# L293.net
KiCad netlist of a schematic drawn in EAGLE
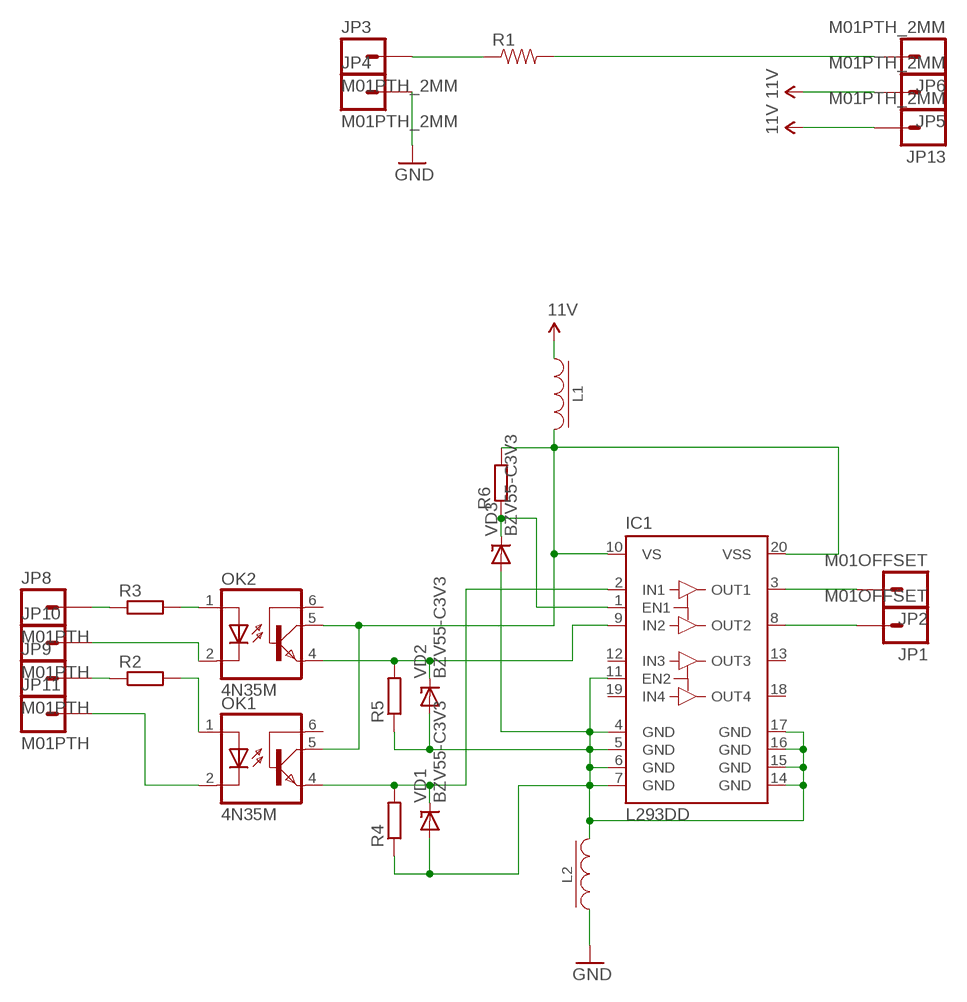
[diagram p0: schematic, sheet 1]

(export (version "E")
  (design (tool "Eeschema 10.0.6"))
  (components
    (comp (ref "IC1")
      (value "L293DD")
      (footprint "eagle-import:SO20")
      (libsource (lib "eagle-import") (part "L293DD"))
    )
    (comp (ref "JP1")
      (value "M01OFFSET")
      (footprint "eagle-import:1X01_OFFSET")
      (libsource (lib "eagle-import") (part "M01OFFSET"))
    )
    (comp (ref "JP2")
      (value "M01OFFSET")
      (footprint "eagle-import:1X01_OFFSET")
      (libsource (lib "eagle-import") (part "M01OFFSET"))
    )
    (comp (ref "JP3")
      (value "M01PTH_2MM")
      (footprint "eagle-import:1X01_2MM")
      (libsource (lib "eagle-import") (part "M01PTH_2MM"))
    )
    (comp (ref "JP4")
      (value "M01PTH_2MM")
      (footprint "eagle-import:1X01_2MM")
      (libsource (lib "eagle-import") (part "M01PTH_2MM"))
    )
    (comp (ref "JP5")
      (value "M01PTH_2MM")
      (footprint "eagle-import:1X01_2MM")
      (libsource (lib "eagle-import") (part "M01PTH_2MM"))
    )
    (comp (ref "JP6")
      (value "M01PTH_2MM")
      (footprint "eagle-import:1X01_2MM")
      (libsource (lib "eagle-import") (part "M01PTH_2MM"))
    )
    (comp (ref "JP8")
      (value "M01PTH")
      (footprint "eagle-import:1X01")
      (libsource (lib "eagle-import") (part "M01PTH"))
    )
    (comp (ref "JP9")
      (value "M01PTH")
      (footprint "eagle-import:1X01")
      (libsource (lib "eagle-import") (part "M01PTH"))
    )
    (comp (ref "JP10")
      (value "M01PTH")
      (footprint "eagle-import:1X01")
      (libsource (lib "eagle-import") (part "M01PTH"))
    )
    (comp (ref "JP11")
      (value "M01PTH")
      (footprint "eagle-import:1X01")
      (libsource (lib "eagle-import") (part "M01PTH"))
    )
    (comp (ref "JP13")
      (value "M01PTH_2MM")
      (footprint "eagle-import:1X01_2MM")
      (libsource (lib "eagle-import") (part "M01PTH_2MM"))
    )
    (comp (ref "L1")
      (value "DRA127")
      (footprint "eagle-import:DRA127")
      (libsource (lib "eagle-import") (part "DRA127"))
    )
    (comp (ref "L2")
      (value "DRA127")
      (footprint "eagle-import:DRA127")
      (libsource (lib "eagle-import") (part "DRA127"))
    )
    (comp (ref "OK1")
      (value "4N35M")
      (footprint "eagle-import:DIL06")
      (fields (field (name "MPN") "4N35-M"))
      (libsource (lib "eagle-import") (part "4N?M35"))
    )
    (comp (ref "OK2")
      (value "4N35M")
      (footprint "eagle-import:DIL06")
      (fields (field (name "MPN") "4N35-M"))
      (libsource (lib "eagle-import") (part "4N?M35"))
    )
    (comp (ref "R1")
      (value "RESISTOR2512")
      (footprint "eagle-import:R2512")
      (libsource (lib "eagle-import") (part "RESISTOR2512"))
    )
    (comp (ref "R2")
      (value "RESISTOR0805")
      (footprint "eagle-import:0805")
      (libsource (lib "eagle-import") (part "RESISTOR0805"))
    )
    (comp (ref "R3")
      (value "RESISTOR0805")
      (footprint "eagle-import:0805")
      (libsource (lib "eagle-import") (part "RESISTOR0805"))
    )
    (comp (ref "R4")
      (value "RESISTOR0805")
      (footprint "eagle-import:0805")
      (libsource (lib "eagle-import") (part "RESISTOR0805"))
    )
    (comp (ref "R5")
      (value "RESISTOR0805")
      (footprint "eagle-import:0805")
      (libsource (lib "eagle-import") (part "RESISTOR0805"))
    )
    (comp (ref "R6")
      (value "RESISTOR0805")
      (footprint "eagle-import:0805")
      (libsource (lib "eagle-import") (part "RESISTOR0805"))
    )
    (comp (ref "VD1")
      (value "BZV55-C3V3")
      (footprint "eagle-import:SOD80C")
      (fields (field (name "PARTNO") "?"))
      (libsource (lib "eagle-import") (part "BZV55-C3V3"))
    )
    (comp (ref "VD2")
      (value "BZV55-C3V3")
      (footprint "eagle-import:SOD80C")
      (fields (field (name "PARTNO") "?"))
      (libsource (lib "eagle-import") (part "BZV55-C3V3"))
    )
    (comp (ref "VD3")
      (value "BZV55-C3V3")
      (footprint "eagle-import:SOD80C")
      (fields (field (name "PARTNO") "?"))
      (libsource (lib "eagle-import") (part "BZV55-C3V3"))
    )
  )
  (nets
    (net (code "1") (name "11V") (class "Default")
      (node (ref "JP13") (pin "1") (pinfunction "1_1") (pintype "passive"))
      (node (ref "JP5") (pin "1") (pinfunction "1_1") (pintype "passive"))
      (node (ref "L1") (pin "1") (pinfunction "1_1") (pintype "passive"))
    )
    (net (code "2") (name "GND") (class "Default")
      (node (ref "JP4") (pin "1") (pinfunction "1_1") (pintype "passive"))
      (node (ref "L2") (pin "1") (pinfunction "1_1") (pintype "passive"))
    )
    (net (code "3") (name "Net-(IC1-EN1)") (class "Default")
      (node (ref "IC1") (pin "1") (pinfunction "EN1_1") (pintype "input"))
      (node (ref "R6") (pin "1") (pinfunction "1_1") (pintype "passive"))
      (node (ref "VD3") (pin "C") (pinfunction "C_C") (pintype "passive"))
    )
    (net (code "4") (name "Net-(IC1-EN2)") (class "Default")
      (node (ref "IC1") (pin "11") (pinfunction "EN2_11") (pintype "input"))
      (node (ref "IC1") (pin "14") (pinfunction "GND_14") (pintype "power_in"))
      (node (ref "IC1") (pin "15") (pinfunction "GND_15") (pintype "power_in"))
      (node (ref "IC1") (pin "16") (pinfunction "GND_16") (pintype "power_in"))
      (node (ref "IC1") (pin "17") (pinfunction "GND_17") (pintype "power_in"))
      (node (ref "IC1") (pin "4") (pinfunction "GND_4") (pintype "power_in"))
      (node (ref "IC1") (pin "5") (pinfunction "GND_5") (pintype "power_in"))
      (node (ref "IC1") (pin "6") (pinfunction "GND_6") (pintype "power_in"))
      (node (ref "IC1") (pin "7") (pinfunction "GND_7") (pintype "power_in"))
      (node (ref "L2") (pin "2") (pinfunction "2_2") (pintype "passive"))
      (node (ref "R4") (pin "1") (pinfunction "1_1") (pintype "passive"))
      (node (ref "R5") (pin "1") (pinfunction "1_1") (pintype "passive"))
      (node (ref "VD1") (pin "A") (pinfunction "A_A") (pintype "passive"))
      (node (ref "VD2") (pin "A") (pinfunction "A_A") (pintype "passive"))
      (node (ref "VD3") (pin "A") (pinfunction "A_A") (pintype "passive"))
    )
    (net (code "5") (name "Net-(IC1-IN1)") (class "Default")
      (node (ref "IC1") (pin "2") (pinfunction "IN1_2") (pintype "input"))
      (node (ref "OK1") (pin "4") (pinfunction "EMI_4") (pintype "passive"))
      (node (ref "R4") (pin "2") (pinfunction "2_2") (pintype "passive"))
      (node (ref "VD1") (pin "C") (pinfunction "C_C") (pintype "passive"))
    )
    (net (code "6") (name "Net-(IC1-IN2)") (class "Default")
      (node (ref "IC1") (pin "9") (pinfunction "IN2_9") (pintype "input"))
      (node (ref "OK2") (pin "4") (pinfunction "EMI_4") (pintype "passive"))
      (node (ref "R5") (pin "2") (pinfunction "2_2") (pintype "passive"))
      (node (ref "VD2") (pin "C") (pinfunction "C_C") (pintype "passive"))
    )
    (net (code "7") (name "Net-(IC1-OUT1)") (class "Default")
      (node (ref "IC1") (pin "3") (pinfunction "OUT1_3") (pintype "output"))
      (node (ref "JP2") (pin "1") (pinfunction "1_1") (pintype "passive"))
    )
    (net (code "8") (name "Net-(IC1-OUT2)") (class "Default")
      (node (ref "IC1") (pin "8") (pinfunction "OUT2_8") (pintype "output"))
      (node (ref "JP1") (pin "1") (pinfunction "1_1") (pintype "passive"))
    )
    (net (code "9") (name "Net-(IC1-VS)") (class "Default")
      (node (ref "IC1") (pin "10") (pinfunction "VS_10") (pintype "power_in"))
      (node (ref "IC1") (pin "20") (pinfunction "VSS_20") (pintype "power_in"))
      (node (ref "L1") (pin "2") (pinfunction "2_2") (pintype "passive"))
      (node (ref "OK1") (pin "5") (pinfunction "COL_5") (pintype "passive"))
      (node (ref "OK2") (pin "5") (pinfunction "COL_5") (pintype "passive"))
      (node (ref "R6") (pin "2") (pinfunction "2_2") (pintype "passive"))
    )
    (net (code "10") (name "Net-(JP3-Pad1)") (class "Default")
      (node (ref "JP3") (pin "1") (pinfunction "1_1") (pintype "passive"))
      (node (ref "R1") (pin "1") (pinfunction "1_1") (pintype "passive"))
    )
    (net (code "11") (name "Net-(JP6-Pad1)") (class "Default")
      (node (ref "JP6") (pin "1") (pinfunction "1_1") (pintype "passive"))
      (node (ref "R1") (pin "2") (pinfunction "2_2") (pintype "passive"))
    )
    (net (code "12") (name "Net-(JP8-Pad1)") (class "Default")
      (node (ref "JP8") (pin "1") (pinfunction "1_1") (pintype "passive"))
      (node (ref "R3") (pin "1") (pinfunction "1_1") (pintype "passive"))
    )
    (net (code "13") (name "Net-(JP9-Pad1)") (class "Default")
      (node (ref "JP9") (pin "1") (pinfunction "1_1") (pintype "passive"))
      (node (ref "R2") (pin "1") (pinfunction "1_1") (pintype "passive"))
    )
    (net (code "14") (name "Net-(OK1-A)") (class "Default")
      (node (ref "OK1") (pin "1") (pinfunction "A_1") (pintype "passive"))
      (node (ref "R2") (pin "2") (pinfunction "2_2") (pintype "passive"))
    )
    (net (code "15") (name "Net-(OK1-C)") (class "Default")
      (node (ref "JP11") (pin "1") (pinfunction "1_1") (pintype "passive"))
      (node (ref "OK1") (pin "2") (pinfunction "C_2") (pintype "passive"))
    )
    (net (code "16") (name "Net-(OK2-A)") (class "Default")
      (node (ref "OK2") (pin "1") (pinfunction "A_1") (pintype "passive"))
      (node (ref "R3") (pin "2") (pinfunction "2_2") (pintype "passive"))
    )
    (net (code "17") (name "Net-(OK2-C)") (class "Default")
      (node (ref "JP10") (pin "1") (pinfunction "1_1") (pintype "passive"))
      (node (ref "OK2") (pin "2") (pinfunction "C_2") (pintype "passive"))
    )
    (net (code "18") (name "unconnected-(IC1-IN3-Pad12)") (class "Default")
      (node (ref "IC1") (pin "12") (pinfunction "IN3_12") (pintype "input"))
    )
    (net (code "19") (name "unconnected-(IC1-IN4-Pad19)") (class "Default")
      (node (ref "IC1") (pin "19") (pinfunction "IN4_19") (pintype "input"))
    )
    (net (code "20") (name "unconnected-(IC1-OUT3-Pad13)") (class "Default")
      (node (ref "IC1") (pin "13") (pinfunction "OUT3_13") (pintype "output"))
    )
    (net (code "21") (name "unconnected-(IC1-OUT4-Pad18)") (class "Default")
      (node (ref "IC1") (pin "18") (pinfunction "OUT4_18") (pintype "output"))
    )
    (net (code "22") (name "unconnected-(OK1-BAS-Pad6)") (class "Default")
      (node (ref "OK1") (pin "6") (pinfunction "BAS_6") (pintype "passive"))
    )
    (net (code "23") (name "unconnected-(OK2-BAS-Pad6)") (class "Default")
      (node (ref "OK2") (pin "6") (pinfunction "BAS_6") (pintype "passive"))
    )
  )
)
